# permacam.net
KiCad netlist of a schematic drawn in EAGLE
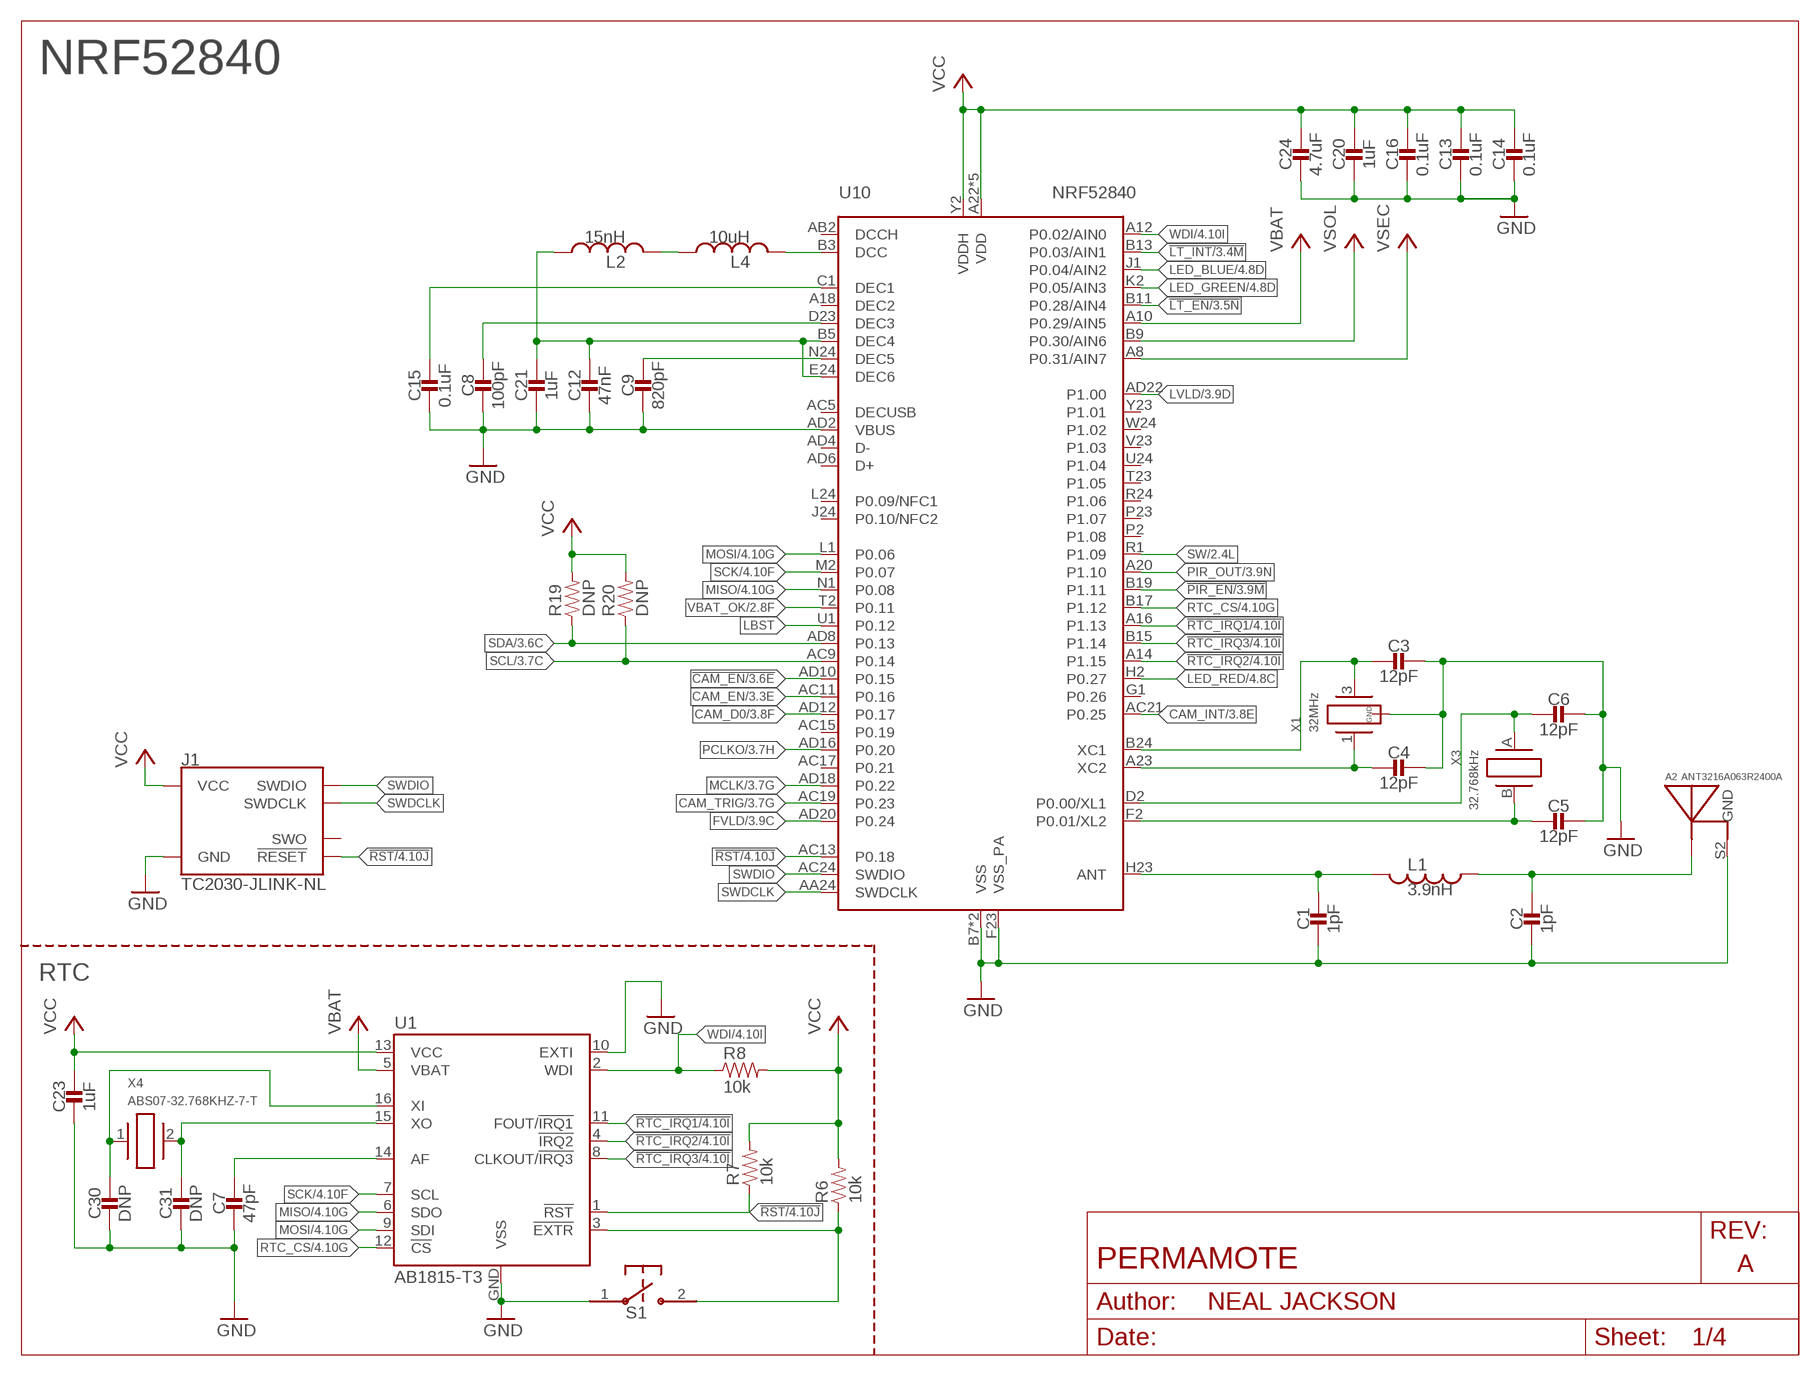
[diagram p0: schematic, sheet 1]
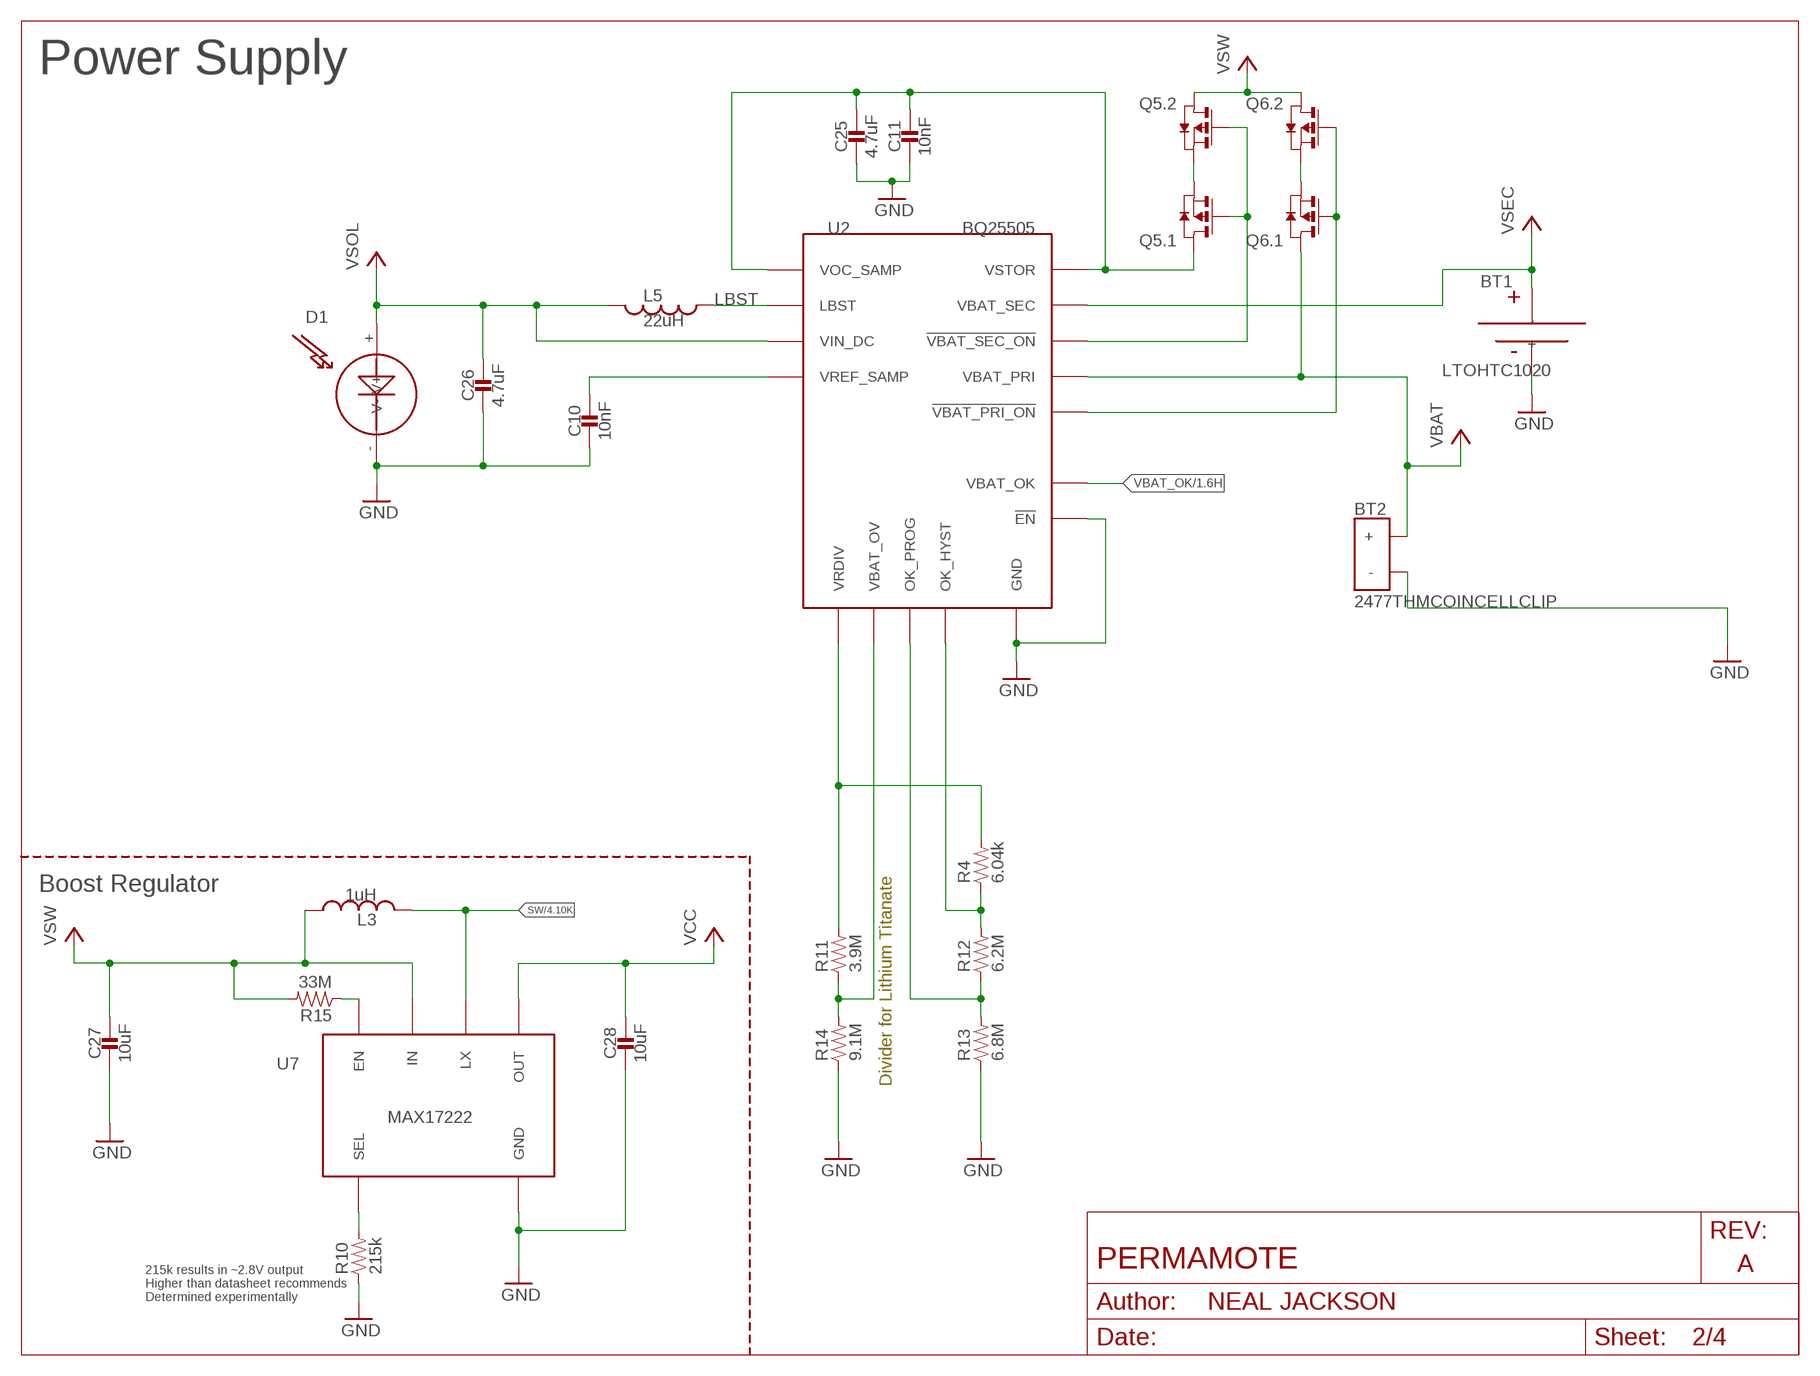
[diagram p1: schematic, sheet 2]
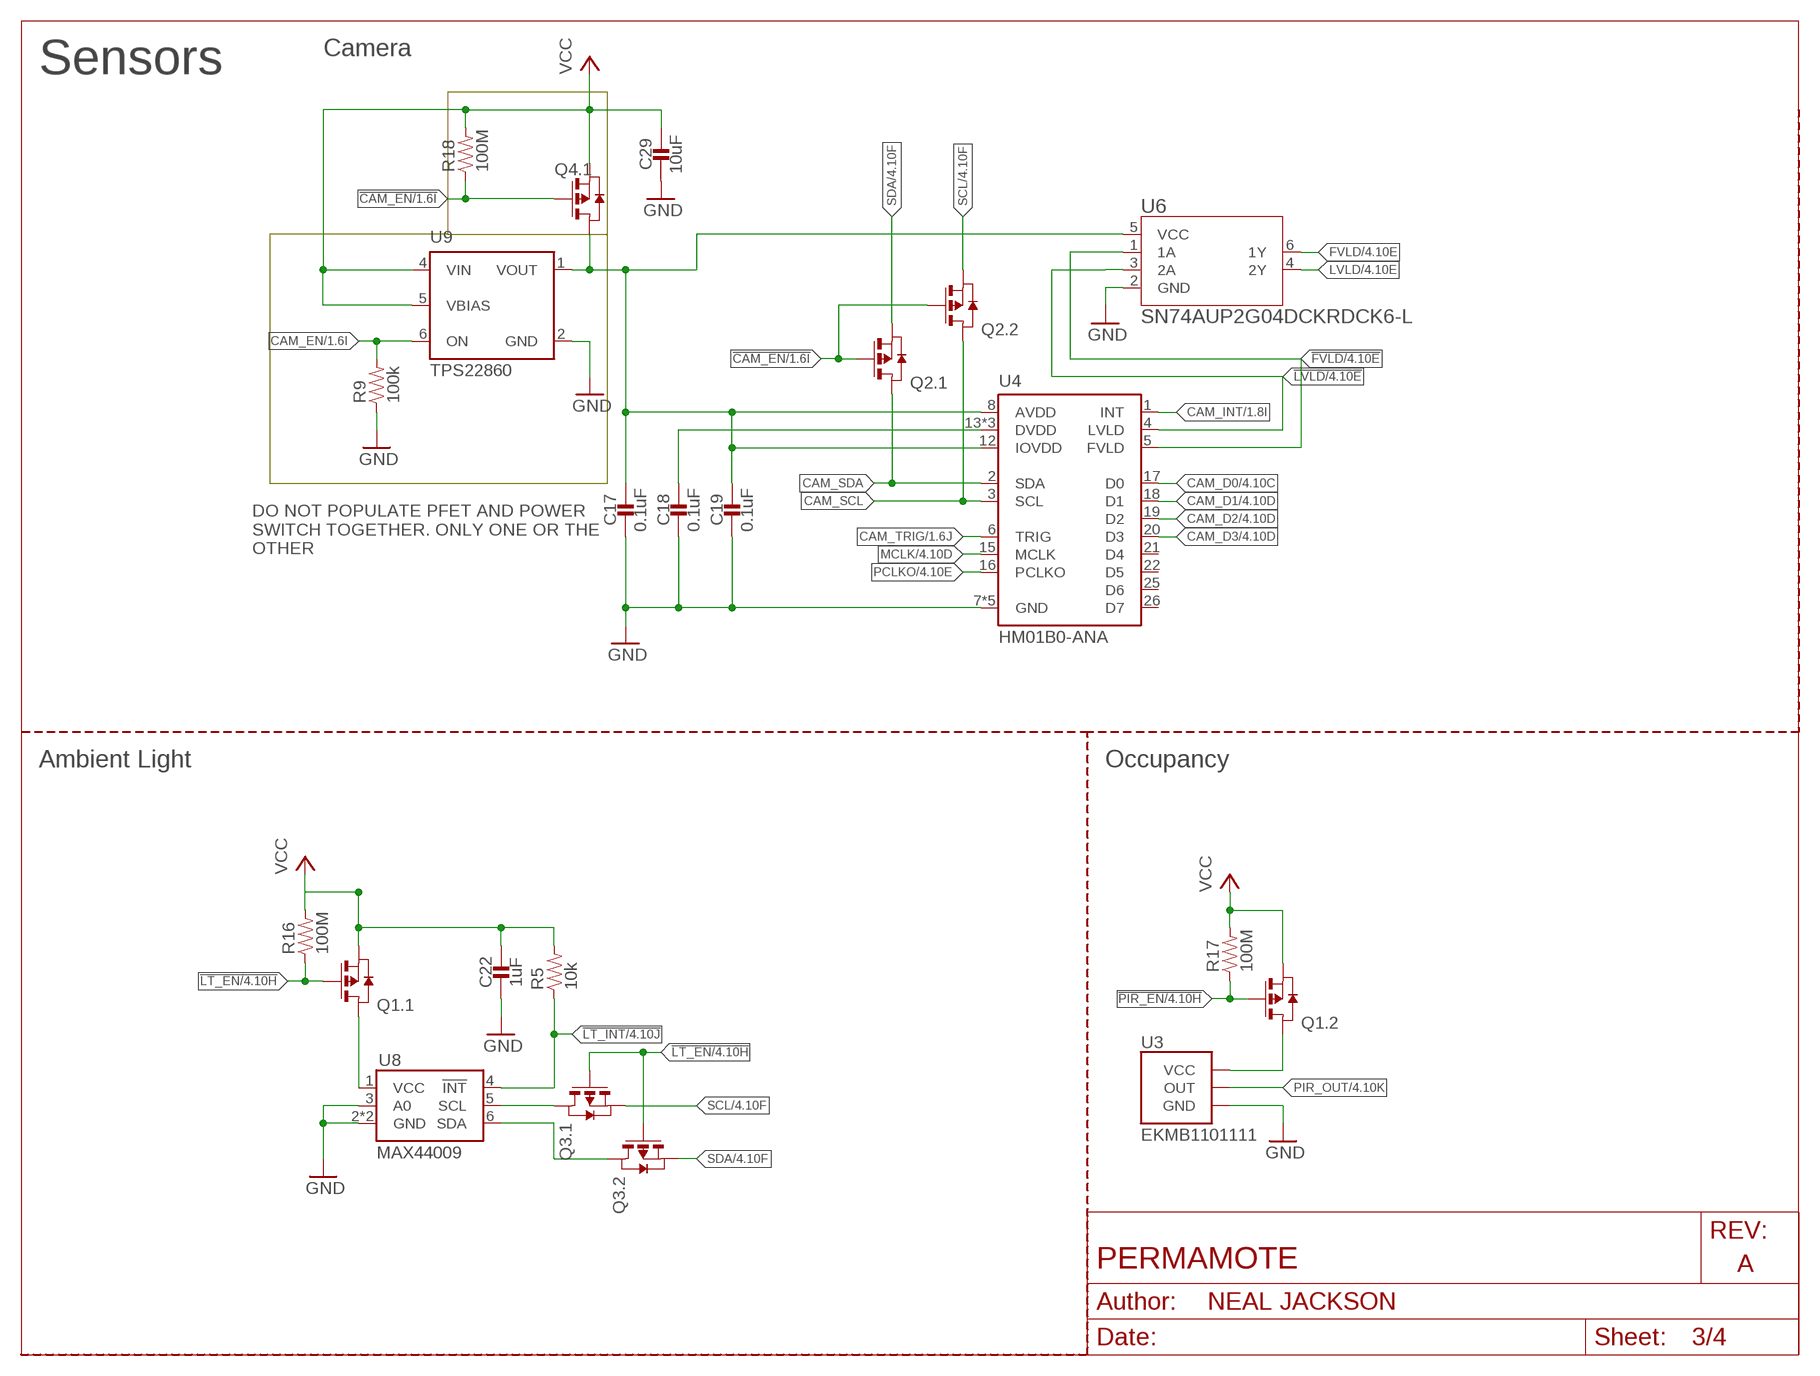
[diagram p2: schematic, sheet 3]
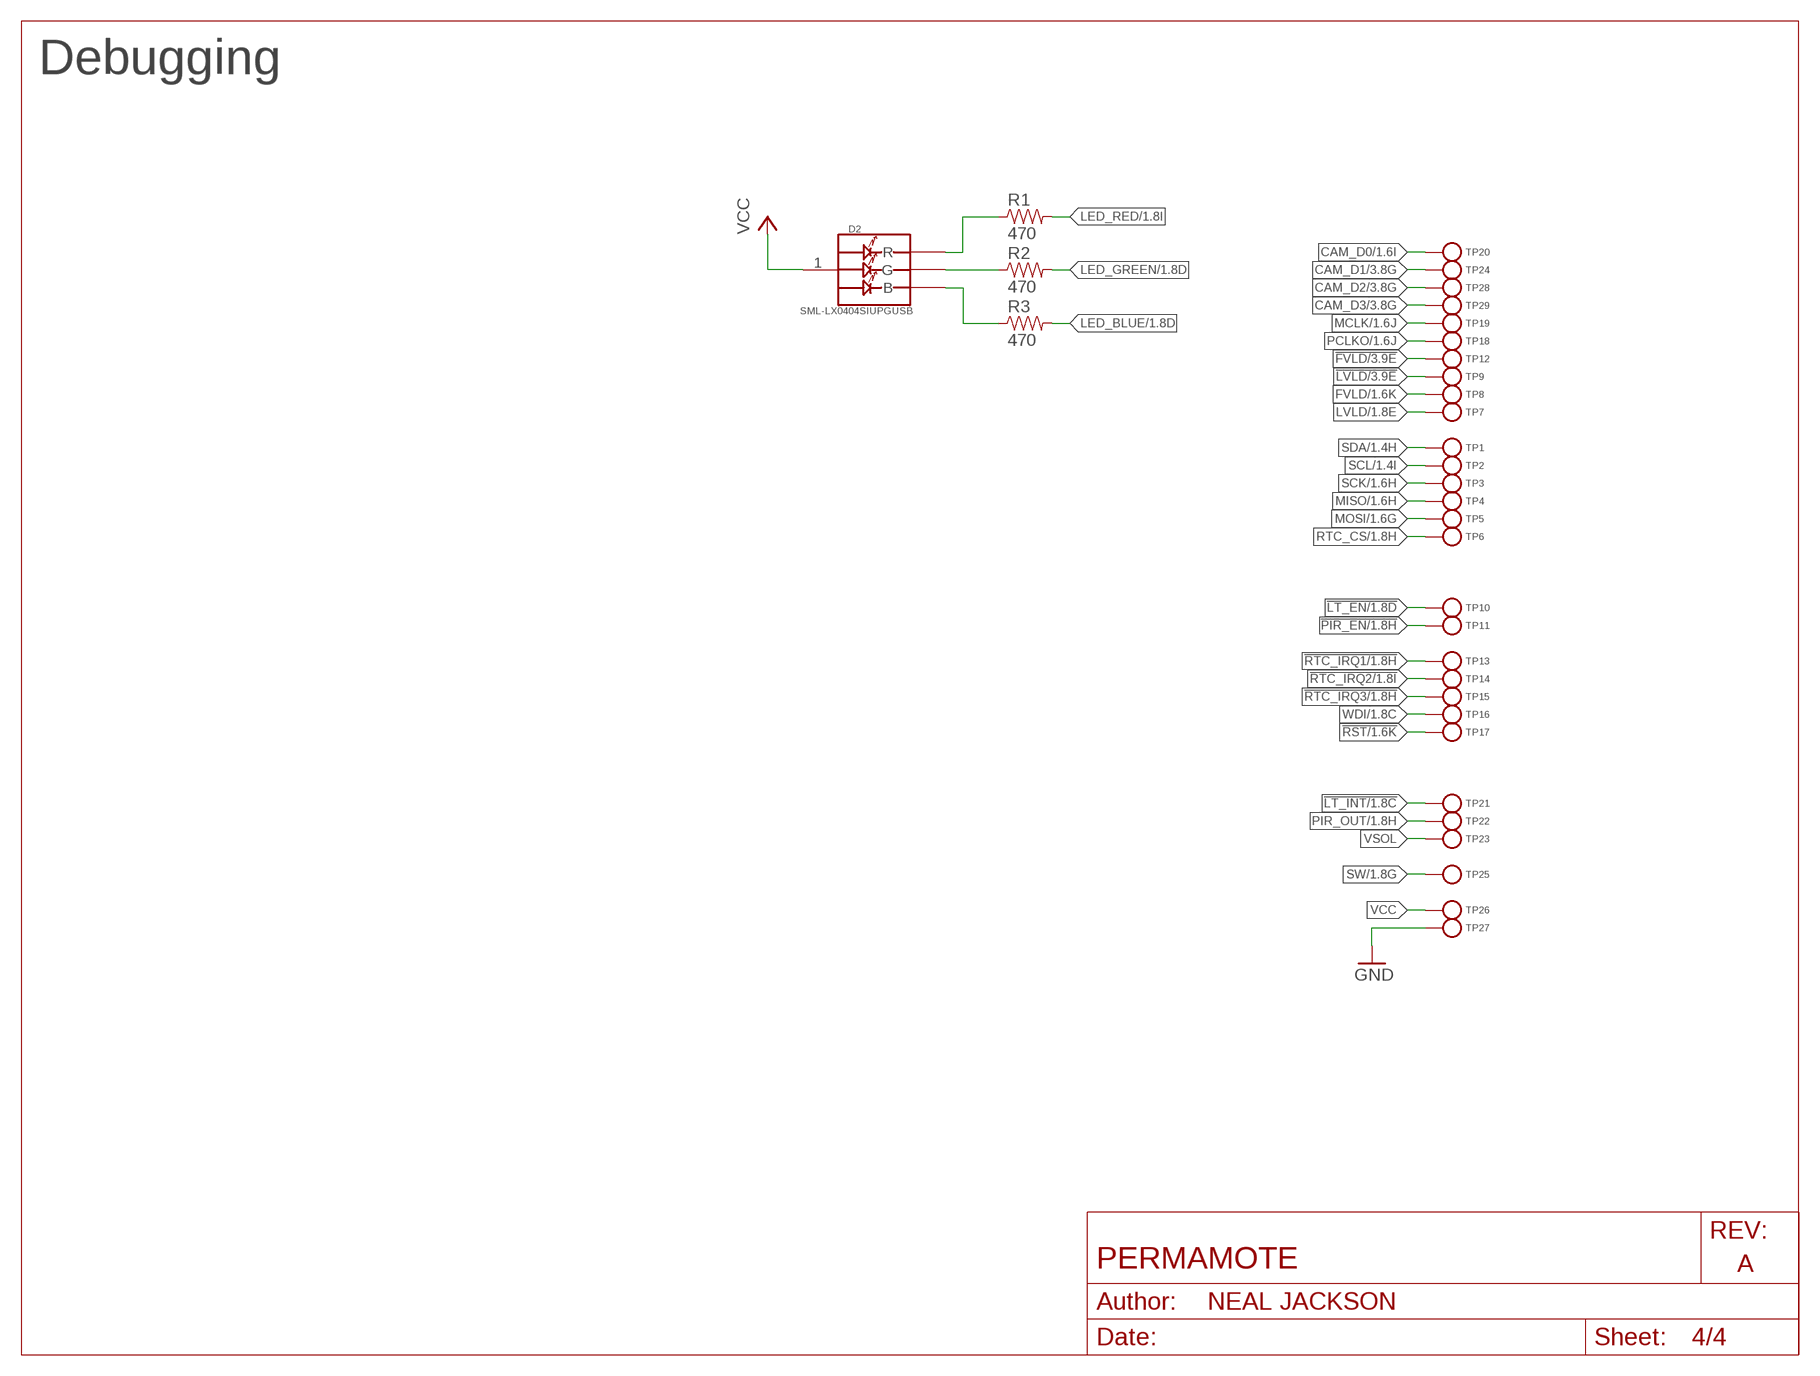
[diagram p3: schematic, sheet 4]

(export (version "E")
  (design (tool "Eeschema 10.0.6"))
  (components
    (comp (ref "C17")
      (value "0.1uF")
      (footprint "eagle-import:0402_CAP")
      (fields (field (name "MPN") "GRM155R71C104KA88J "))
      (libsource (lib "eagle-import") (part "CAPACITOR0402_CAP"))
    )
    (comp (ref "C18")
      (value "0.1uF")
      (footprint "eagle-import:0402_CAP")
      (fields (field (name "MPN") "GRM155R71C104KA88J "))
      (libsource (lib "eagle-import") (part "CAPACITOR0402_CAP"))
    )
    (comp (ref "C19")
      (value "0.1uF")
      (footprint "eagle-import:0402_CAP")
      (fields (field (name "MPN") "GRM155R71C104KA88J "))
      (libsource (lib "eagle-import") (part "CAPACITOR0402_CAP"))
    )
    (comp (ref "C22")
      (value "1uF")
      (footprint "eagle-import:0402_CAP")
      (fields (field (name "MPN") "GRM155R70G105KA12D "))
      (libsource (lib "eagle-import") (part "CAPACITOR0402_CAP"))
    )
    (comp (ref "C29")
      (value "10uF")
      (footprint "eagle-import:0603_CAP")
      (fields (field (name "MPN") "GRM188R60J106ME47D "))
      (libsource (lib "eagle-import") (part "CAPACITOR0603_CAP"))
    )
    (comp (ref "Q1")
      (value "PMDXB950UPEL")
      (footprint "eagle-import:XDFN-6")
      (fields (field (name "MANUFACTURER") "NEXPERIA") (field (name "MPN") "PMDXB950UPELZ"))
      (libsource (lib "eagle-import") (part "PMDXB950UPEL"))
    )
    (comp (ref "Q2")
      (value "PMDXB950UPEL")
      (footprint "eagle-import:XDFN-6")
      (fields (field (name "MANUFACTURER") "NEXPERIA") (field (name "MPN") "PMDXB950UPELZ"))
      (libsource (lib "eagle-import") (part "PMDXB950UPEL"))
    )
    (comp (ref "Q3")
      (value "PMDXB950UPEL")
      (footprint "eagle-import:XDFN-6")
      (fields (field (name "MANUFACTURER") "NEXPERIA") (field (name "MPN") "PMDXB950UPELZ"))
      (libsource (lib "eagle-import") (part "PMDXB950UPEL"))
    )
    (comp (ref "Q4")
      (value "PMDXB950UPEL")
      (footprint "eagle-import:XDFN-6")
      (fields (field (name "MANUFACTURER") "NEXPERIA") (field (name "MPN") "PMDXB950UPELZ"))
      (libsource (lib "eagle-import") (part "PMDXB950UPEL"))
    )
    (comp (ref "R5")
      (value "10k")
      (footprint "eagle-import:0402_RES")
      (fields (field (name "MPN") "RC0402JR-0710KL"))
      (libsource (lib "eagle-import") (part "RESISTOR0402_RES"))
    )
    (comp (ref "R9")
      (value "100k")
      (footprint "eagle-import:0402_RES")
      (fields (field (name "MPN") "RC0402JR-07100KL"))
      (libsource (lib "eagle-import") (part "RESISTOR0402_RES"))
    )
    (comp (ref "R16")
      (value "100M")
      (footprint "eagle-import:0402_RES")
      (fields (field (name "MPN") "HMC0402JT100M "))
      (libsource (lib "eagle-import") (part "RESISTOR0402_RES"))
    )
    (comp (ref "R17")
      (value "100M")
      (footprint "eagle-import:0402_RES")
      (fields (field (name "MPN") "HMC0402JT100M "))
      (libsource (lib "eagle-import") (part "RESISTOR0402_RES"))
    )
    (comp (ref "R18")
      (value "100M")
      (footprint "eagle-import:0402_RES")
      (fields (field (name "MPN") "HMC0402JT100M "))
      (libsource (lib "eagle-import") (part "RESISTOR0402_RES"))
    )
    (comp (ref "U3")
      (value "EKMB1101111")
      (footprint "eagle-import:AMN2")
      (fields (field (name "MANUFACTURER") "PANASONIC"))
      (libsource (lib "eagle-import") (part "EKMB1101111"))
    )
    (comp (ref "U4")
      (value "HM01B0-ANA")
      (footprint "eagle-import:NEOPAC-26")
      (fields (field (name "MPN") "HMB01B0-ANA"))
      (libsource (lib "eagle-import") (part "HM01B0-ANA"))
    )
    (comp (ref "U6")
      (value "SN74AUP2G04DCKRDCK6-L")
      (footprint "eagle-import:DCK6-L")
      (fields (field (name "MANUFACTURER_PART_NUMBER") "SN74AUP2G04DCKR"))
      (libsource (lib "eagle-import") (part "SN74AUP2G04DCKRDCK6-L"))
    )
    (comp (ref "U8")
      (value "MAX44009")
      (footprint "eagle-import:UDFN-6-EXPOSED")
      (fields (field (name "MANUFACTURER") "MAXIM") (field (name "MPN") "MAX44009EDT+T"))
      (libsource (lib "eagle-import") (part "MAX44009"))
    )
    (comp (ref "U9")
      (value "TPS22860")
      (footprint "eagle-import:SOT-23-6")
      (fields (field (name "MPN") "TPS22860DBVR"))
      (libsource (lib "eagle-import") (part "TPS22860"))
    )
    (comp (ref "D2")
      (value "SML-LX0404SIUPGUSB")
      (footprint "eagle-import:1MM_SQ_4PAD")
      (fields (field (name "MANUFACTURER") "Lumex Opto"))
      (libsource (lib "eagle-import") (part "SML-LX0404SIUPGUSB"))
    )
    (comp (ref "R1")
      (value "470")
      (footprint "eagle-import:0402_RES")
      (fields (field (name "MPN") "RC0402JR-07470RL "))
      (libsource (lib "eagle-import") (part "RESISTOR0402_RES"))
    )
    (comp (ref "R2")
      (value "470")
      (footprint "eagle-import:0402_RES")
      (fields (field (name "MPN") "RC0402JR-07470RL "))
      (libsource (lib "eagle-import") (part "RESISTOR0402_RES"))
    )
    (comp (ref "R3")
      (value "470")
      (footprint "eagle-import:0402_RES")
      (fields (field (name "MPN") "RC0402JR-07470RL "))
      (libsource (lib "eagle-import") (part "RESISTOR0402_RES"))
    )
    (comp (ref "TP1")
      (value "TEST-POINT")
      (footprint "eagle-import:PAD.03X.03")
      (libsource (lib "eagle-import") (part "TEST-POINT"))
    )
    (comp (ref "TP2")
      (value "TEST-POINT")
      (footprint "eagle-import:PAD.03X.03")
      (libsource (lib "eagle-import") (part "TEST-POINT"))
    )
    (comp (ref "TP3")
      (value "TEST-POINT")
      (footprint "eagle-import:PAD.03X.03")
      (libsource (lib "eagle-import") (part "TEST-POINT"))
    )
    (comp (ref "TP4")
      (value "TEST-POINT")
      (footprint "eagle-import:PAD.03X.03")
      (libsource (lib "eagle-import") (part "TEST-POINT"))
    )
    (comp (ref "TP5")
      (value "TEST-POINT")
      (footprint "eagle-import:PAD.03X.03")
      (libsource (lib "eagle-import") (part "TEST-POINT"))
    )
    (comp (ref "TP6")
      (value "TEST-POINT")
      (footprint "eagle-import:PAD.03X.03")
      (libsource (lib "eagle-import") (part "TEST-POINT"))
    )
    (comp (ref "TP7")
      (value "TEST-POINT")
      (footprint "eagle-import:PAD.03X.03")
      (libsource (lib "eagle-import") (part "TEST-POINT"))
    )
    (comp (ref "TP8")
      (value "TEST-POINT")
      (footprint "eagle-import:PAD.03X.03")
      (libsource (lib "eagle-import") (part "TEST-POINT"))
    )
    (comp (ref "TP9")
      (value "TEST-POINT")
      (footprint "eagle-import:PAD.03X.03")
      (libsource (lib "eagle-import") (part "TEST-POINT"))
    )
    (comp (ref "TP10")
      (value "TEST-POINT")
      (footprint "eagle-import:PAD.03X.03")
      (libsource (lib "eagle-import") (part "TEST-POINT"))
    )
    (comp (ref "TP11")
      (value "TEST-POINT")
      (footprint "eagle-import:PAD.03X.03")
      (libsource (lib "eagle-import") (part "TEST-POINT"))
    )
    (comp (ref "TP12")
      (value "TEST-POINT")
      (footprint "eagle-import:PAD.03X.03")
      (libsource (lib "eagle-import") (part "TEST-POINT"))
    )
    (comp (ref "TP13")
      (value "TEST-POINT")
      (footprint "eagle-import:PAD.03X.03")
      (libsource (lib "eagle-import") (part "TEST-POINT"))
    )
    (comp (ref "TP14")
      (value "TEST-POINT")
      (footprint "eagle-import:PAD.03X.03")
      (libsource (lib "eagle-import") (part "TEST-POINT"))
    )
    (comp (ref "TP15")
      (value "TEST-POINT")
      (footprint "eagle-import:PAD.03X.03")
      (libsource (lib "eagle-import") (part "TEST-POINT"))
    )
    (comp (ref "TP16")
      (value "TEST-POINT")
      (footprint "eagle-import:PAD.03X.03")
      (libsource (lib "eagle-import") (part "TEST-POINT"))
    )
    (comp (ref "TP17")
      (value "TEST-POINT")
      (footprint "eagle-import:PAD.03X.03")
      (libsource (lib "eagle-import") (part "TEST-POINT"))
    )
    (comp (ref "TP18")
      (value "TEST-POINT")
      (footprint "eagle-import:PAD.03X.03")
      (libsource (lib "eagle-import") (part "TEST-POINT"))
    )
    (comp (ref "TP19")
      (value "TEST-POINT")
      (footprint "eagle-import:PAD.03X.03")
      (libsource (lib "eagle-import") (part "TEST-POINT"))
    )
    (comp (ref "TP20")
      (value "TEST-POINT")
      (footprint "eagle-import:PAD.03X.03")
      (libsource (lib "eagle-import") (part "TEST-POINT"))
    )
    (comp (ref "TP21")
      (value "TEST-POINT")
      (footprint "eagle-import:PAD.03X.03")
      (libsource (lib "eagle-import") (part "TEST-POINT"))
    )
    (comp (ref "TP22")
      (value "TEST-POINT")
      (footprint "eagle-import:PAD.03X.03")
      (libsource (lib "eagle-import") (part "TEST-POINT"))
    )
    (comp (ref "TP23")
      (value "TEST-POINT")
      (footprint "eagle-import:PAD.03X.03")
      (libsource (lib "eagle-import") (part "TEST-POINT"))
    )
    (comp (ref "TP24")
      (value "TEST-POINT")
      (footprint "eagle-import:PAD.03X.03")
      (libsource (lib "eagle-import") (part "TEST-POINT"))
    )
    (comp (ref "TP25")
      (value "TEST-POINT")
      (footprint "eagle-import:PAD.03X.03")
      (libsource (lib "eagle-import") (part "TEST-POINT"))
    )
    (comp (ref "TP26")
      (value "TEST-POINT")
      (footprint "eagle-import:PAD.03X.03")
      (libsource (lib "eagle-import") (part "TEST-POINT"))
    )
    (comp (ref "TP27")
      (value "TEST-POINT")
      (footprint "eagle-import:PAD.03X.03")
      (libsource (lib "eagle-import") (part "TEST-POINT"))
    )
    (comp (ref "TP28")
      (value "TEST-POINT")
      (footprint "eagle-import:PAD.03X.03")
      (libsource (lib "eagle-import") (part "TEST-POINT"))
    )
    (comp (ref "TP29")
      (value "TEST-POINT")
      (footprint "eagle-import:PAD.03X.03")
      (libsource (lib "eagle-import") (part "TEST-POINT"))
    )
    (comp (ref "A2")
      (value "ANT3216A063R2400A")
      (footprint "eagle-import:ANT3216A063R2400A")
      (fields (field (name "MANUFACTURER") "YAGEO"))
      (libsource (lib "eagle-import") (part "ANT3216A063R2400A"))
    )
    (comp (ref "C1")
      (value "1pF")
      (footprint "eagle-import:0402_CAP")
      (fields (field (name "MPN") "CL05C010CB5NNNC"))
      (libsource (lib "eagle-import") (part "CAPACITOR0402_CAP"))
    )
    (comp (ref "C2")
      (value "1pF")
      (footprint "eagle-import:0402_CAP")
      (fields (field (name "MPN") "CL05C010CB5NNNC"))
      (libsource (lib "eagle-import") (part "CAPACITOR0402_CAP"))
    )
    (comp (ref "C3")
      (value "12pF")
      (footprint "eagle-import:0402_CAP")
      (fields (field (name "MPN") "GRM1555C1H120GA01D "))
      (libsource (lib "eagle-import") (part "CAPACITOR0402_CAP"))
    )
    (comp (ref "C4")
      (value "12pF")
      (footprint "eagle-import:0402_CAP")
      (fields (field (name "MPN") "GRM1555C1H120GA01D "))
      (libsource (lib "eagle-import") (part "CAPACITOR0402_CAP"))
    )
    (comp (ref "C5")
      (value "12pF")
      (footprint "eagle-import:0402_CAP")
      (fields (field (name "MPN") "GRM1555C1H120GA01D "))
      (libsource (lib "eagle-import") (part "CAPACITOR0402_CAP"))
    )
    (comp (ref "C6")
      (value "12pF")
      (footprint "eagle-import:0402_CAP")
      (fields (field (name "MPN") "GRM1555C1H120GA01D "))
      (libsource (lib "eagle-import") (part "CAPACITOR0402_CAP"))
    )
    (comp (ref "C7")
      (value "47pF")
      (footprint "eagle-import:0402_CAP")
      (fields (field (name "MPN") "GRM1555C1H470JA01D "))
      (libsource (lib "eagle-import") (part "CAPACITOR0402_CAP"))
    )
    (comp (ref "C8")
      (value "100pF")
      (footprint "eagle-import:0402_CAP")
      (fields (field (name "MPN") "GRM1555C1H101JA01D "))
      (libsource (lib "eagle-import") (part "CAPACITOR0402_CAP"))
    )
    (comp (ref "C9")
      (value "820pF")
      (footprint "eagle-import:0402_CAP")
      (fields (field (name "MPN") "CL05B821KO5NNNC"))
      (libsource (lib "eagle-import") (part "CAPACITOR0402_CAP"))
    )
    (comp (ref "C12")
      (value "47nF")
      (footprint "eagle-import:0402_CAP")
      (fields (field (name "MPN") "C1005X7R1C473K050BC "))
      (libsource (lib "eagle-import") (part "CAPACITOR0402_CAP"))
    )
    (comp (ref "C13")
      (value "0.1uF")
      (footprint "eagle-import:0402_CAP")
      (fields (field (name "MPN") "GRM155R71C104KA88J "))
      (libsource (lib "eagle-import") (part "CAPACITOR0402_CAP"))
    )
    (comp (ref "C14")
      (value "0.1uF")
      (footprint "eagle-import:0402_CAP")
      (fields (field (name "MPN") "GRM155R71C104KA88J "))
      (libsource (lib "eagle-import") (part "CAPACITOR0402_CAP"))
    )
    (comp (ref "C15")
      (value "0.1uF")
      (footprint "eagle-import:0402_CAP")
      (fields (field (name "MPN") "GRM155R71C104KA88J "))
      (libsource (lib "eagle-import") (part "CAPACITOR0402_CAP"))
    )
    (comp (ref "C16")
      (value "0.1uF")
      (footprint "eagle-import:0402_CAP")
      (fields (field (name "MPN") "GRM155R71C104KA88J "))
      (libsource (lib "eagle-import") (part "CAPACITOR0402_CAP"))
    )
    (comp (ref "C20")
      (value "1uF")
      (footprint "eagle-import:0402_CAP")
      (fields (field (name "MPN") "GRM155R70G105KA12D "))
      (libsource (lib "eagle-import") (part "CAPACITOR0402_CAP"))
    )
    (comp (ref "C21")
      (value "1uF")
      (footprint "eagle-import:0402_CAP")
      (fields (field (name "MPN") "GRM155R70G105KA12D "))
      (libsource (lib "eagle-import") (part "CAPACITOR0402_CAP"))
    )
    (comp (ref "C23")
      (value "1uF")
      (footprint "eagle-import:0402_CAP")
      (fields (field (name "MPN") "GRM155R70G105KA12D "))
      (libsource (lib "eagle-import") (part "CAPACITOR0402_CAP"))
    )
    (comp (ref "C24")
      (value "4.7uF")
      (footprint "eagle-import:0402_CAP")
      (fields (field (name "MPN") "C1005X5R0J475K050BC "))
      (libsource (lib "eagle-import") (part "CAPACITOR0402_CAP"))
    )
    (comp (ref "C30")
      (value "DNP")
      (footprint "eagle-import:0402_CAP")
      (libsource (lib "eagle-import") (part "CAPACITOR0402_CAP"))
    )
    (comp (ref "C31")
      (value "DNP")
      (footprint "eagle-import:0402_CAP")
      (libsource (lib "eagle-import") (part "CAPACITOR0402_CAP"))
    )
    (comp (ref "J1")
      (value "TC2030-JLINK-NL")
      (footprint "eagle-import:TC2030-IDC-NL")
      (libsource (lib "eagle-import") (part "TC2030-JLINK-NL"))
    )
    (comp (ref "L1")
      (value "3.9nH")
      (footprint "eagle-import:0402_CAP")
      (fields (field (name "MPN") "LQP15MN3N9B02D"))
      (libsource (lib "eagle-import") (part "INDUCTOR0402"))
    )
    (comp (ref "L2")
      (value "15nH")
      (footprint "eagle-import:0402_CAP")
      (fields (field (name "MPN") "HK100515NJ-T "))
      (libsource (lib "eagle-import") (part "INDUCTOR0402"))
    )
    (comp (ref "L4")
      (value "10uH")
      (footprint "eagle-import:0603_CAP")
      (fields (field (name "MPN") "LQM18FN100M00D "))
      (libsource (lib "eagle-import") (part "INDUCTOR0603"))
    )
    (comp (ref "R6")
      (value "10k")
      (footprint "eagle-import:0402_RES")
      (fields (field (name "MPN") "RC0402JR-0710KL"))
      (libsource (lib "eagle-import") (part "RESISTOR0402_RES"))
    )
    (comp (ref "R7")
      (value "10k")
      (footprint "eagle-import:0402_RES")
      (fields (field (name "MPN") "RC0402JR-0710KL"))
      (libsource (lib "eagle-import") (part "RESISTOR0402_RES"))
    )
    (comp (ref "R8")
      (value "10k")
      (footprint "eagle-import:0402_RES")
      (fields (field (name "MPN") "RC0402JR-0710KL"))
      (libsource (lib "eagle-import") (part "RESISTOR0402_RES"))
    )
    (comp (ref "R19")
      (value "DNP")
      (footprint "eagle-import:0402_RES")
      (libsource (lib "eagle-import") (part "RESISTOR0402_RES"))
    )
    (comp (ref "R20")
      (value "DNP")
      (footprint "eagle-import:0402_RES")
      (libsource (lib "eagle-import") (part "RESISTOR0402_RES"))
    )
    (comp (ref "S1")
      (value "B3U-1000P")
      (footprint "eagle-import:B3U-1000P")
      (fields (field (name "MANUFACTURER") "Omron"))
      (libsource (lib "eagle-import") (part "B3U-1000P"))
    )
    (comp (ref "U1")
      (value "AB1815-T3")
      (footprint "eagle-import:QFN-16-3MM")
      (fields (field (name "MANUFACTURER") "Abracon"))
      (libsource (lib "eagle-import") (part "AB1815-T3"))
    )
    (comp (ref "U10")
      (value "NRF52840")
      (footprint "eagle-import:AQFN73")
      (fields (field (name "MANUFACTURER") "NORIDIC SEMICONDUCTOR"))
      (libsource (lib "eagle-import") (part "NRF52840"))
    )
    (comp (ref "X1")
      (value "32MHz")
      (footprint "eagle-import:TXC-7V")
      (fields (field (name "MANUFACTURER") "TXC CORPORATION") (field (name "MPN") "7M-32.000MAHV-T"))
      (libsource (lib "eagle-import") (part "7V-32.000MAHV-T"))
    )
    (comp (ref "X3")
      (value "32.768kHz")
      (footprint "eagle-import:ABS05")
      (fields (field (name "MANUFACTURER") "Abracon") (field (name "MPN") "ABS05-32.768KHZ-9-T"))
      (libsource (lib "eagle-import") (part "ABS05-32.768KHZ-9-T"))
    )
    (comp (ref "X4")
      (value "ABS07-32.768KHZ-7-T")
      (footprint "eagle-import:2-SMD")
      (fields (field (name "MANUFACTURER") "ABRACON") (field (name "MPN") "ABS07-32.768KHZ-7-T "))
      (libsource (lib "eagle-import") (part "ABS07-32.768KHZ-7-T"))
    )
    (comp (ref "BT1")
      (value "LTOHTC1020")
      (footprint "eagle-import:1020")
      (libsource (lib "eagle-import") (part "LTOHTC1020"))
    )
    (comp (ref "BT2")
      (value "2477THMCOINCELLCLIP")
      (footprint "eagle-import:2477THMCOINCLIP")
      (fields (field (name "MANUFACTURER") "Keystone") (field (name "MPN") "3039"))
      (libsource (lib "eagle-import") (part "2477THMCOINCELLCLIP"))
    )
    (comp (ref "C10")
      (value "10nF")
      (footprint "eagle-import:0402_CAP")
      (fields (field (name "MPN") "GRM155R71H103KA88D "))
      (libsource (lib "eagle-import") (part "CAPACITOR0402_CAP"))
    )
    (comp (ref "C11")
      (value "10nF")
      (footprint "eagle-import:0402_CAP")
      (fields (field (name "MPN") "GRM155R71H103KA88D "))
      (libsource (lib "eagle-import") (part "CAPACITOR0402_CAP"))
    )
    (comp (ref "C25")
      (value "4.7uF")
      (footprint "eagle-import:0402_CAP")
      (fields (field (name "MPN") "C1005X5R0J475K050BC "))
      (libsource (lib "eagle-import") (part "CAPACITOR0402_CAP"))
    )
    (comp (ref "C26")
      (value "4.7uF")
      (footprint "eagle-import:0402_CAP")
      (fields (field (name "MPN") "C1005X5R0J475K050BC "))
      (libsource (lib "eagle-import") (part "CAPACITOR0402_CAP"))
    )
    (comp (ref "C27")
      (value "10uF")
      (footprint "eagle-import:0603_CAP")
      (fields (field (name "MPN") "GRM188R60J106ME47D "))
      (libsource (lib "eagle-import") (part "CAPACITOR0603_CAP"))
    )
    (comp (ref "C28")
      (value "10uF")
      (footprint "eagle-import:0603_CAP")
      (fields (field (name "MPN") "GRM188R60J106ME47D "))
      (libsource (lib "eagle-import") (part "CAPACITOR0603_CAP"))
    )
    (comp (ref "D1")
      (value "SOLARCELLHOLES")
      (footprint "eagle-import:SOLAR_HOLES")
      (fields (field (name "MPN") "AM-1454CA"))
      (libsource (lib "eagle-import") (part "SOLARCELLHOLES"))
    )
    (comp (ref "L3")
      (value "1uH")
      (footprint "eagle-import:IHL-1212BZ-11")
      (fields
        (field (name "MANUFACTURER") "Vishay Dale")
        (field (name "MPN") "IHLP1212BZER2R2M11")
        (field (name "DIGIKEY") "541-1319-1-ND")
        (field (name "MPN_1") "IHLP1212BZER1R0M11")
      )
      (libsource (lib "eagle-import") (part "INDUCTORIHL"))
    )
    (comp (ref "L5")
      (value "22uH")
      (footprint "eagle-import:74437324220")
      (fields (field (name "DIGIKEY") "732-3340-1-ND") (field (name "MPN") "74437324220 "))
      (libsource (lib "eagle-import") (part "INDUCTOR74437324220"))
    )
    (comp (ref "Q5")
      (value "PMDXB950UPEL")
      (footprint "eagle-import:XDFN-6")
      (fields (field (name "MANUFACTURER") "NEXPERIA") (field (name "MPN") "PMDXB950UPELZ"))
      (libsource (lib "eagle-import") (part "PMDXB950UPEL"))
    )
    (comp (ref "Q6")
      (value "PMDXB950UPEL")
      (footprint "eagle-import:XDFN-6")
      (fields (field (name "MANUFACTURER") "NEXPERIA") (field (name "MPN") "PMDXB950UPELZ"))
      (libsource (lib "eagle-import") (part "PMDXB950UPEL"))
    )
    (comp (ref "R4")
      (value "6.04k")
      (footprint "eagle-import:0402_RES")
      (fields (field (name "MPN") "RC0402FR-076K04L"))
      (libsource (lib "eagle-import") (part "RESISTOR0402_RES"))
    )
    (comp (ref "R10")
      (value "215k")
      (footprint "eagle-import:0603-RES")
      (fields (field (name "MPN") "RC0603FR-07215KL"))
      (libsource (lib "eagle-import") (part "RESISTOR0603_RES"))
    )
    (comp (ref "R11")
      (value "3.9M")
      (footprint "eagle-import:0402_RES")
      (fields (field (name "MPN") "RC0402JR-073M9L"))
      (libsource (lib "eagle-import") (part "RESISTOR0402_RES"))
    )
    (comp (ref "R12")
      (value "6.2M")
      (footprint "eagle-import:0402_RES")
      (fields (field (name "MPN") "RC0402JR-076M2L"))
      (libsource (lib "eagle-import") (part "RESISTOR0402_RES"))
    )
    (comp (ref "R13")
      (value "6.8M")
      (footprint "eagle-import:0402_RES")
      (fields (field (name "MPN") "RC0402JR-076M8L"))
      (libsource (lib "eagle-import") (part "RESISTOR0402_RES"))
    )
    (comp (ref "R14")
      (value "9.1M")
      (footprint "eagle-import:0402_RES")
      (fields (field (name "MPN") "RC0402JR-079M1L"))
      (libsource (lib "eagle-import") (part "RESISTOR0402_RES"))
    )
    (comp (ref "R15")
      (value "33M")
      (footprint "eagle-import:0603-RES")
      (fields (field (name "MPN") "HMC0603JT33M0 "))
      (libsource (lib "eagle-import") (part "RESISTOR0603_RES"))
    )
    (comp (ref "U2")
      (value "BQ25505")
      (footprint "eagle-import:S-PVQFN-N20-RGR")
      (fields (field (name "MANUFACTURER") "TI") (field (name "MPN") "BQ25505RGRR"))
      (libsource (lib "eagle-import") (part "BQ25505"))
    )
    (comp (ref "U7")
      (value "MAX17222")
      (footprint "eagle-import:UDFN-6-MAXIM")
      (fields (field (name "MANUFACTURER") "MAXIM INTEGRATED") (field (name "MPN") "MAX17222ELT+T"))
      (libsource (lib "eagle-import") (part "MAX17222"))
    )
  )
  (nets
    (net (code "1") (name "CAM_D0") (class "Default")
      (node (ref "TP20") (pin "P$1") (pinfunction "TESTPOINT_P$1") (pintype "bidirectional"))
      (node (ref "U10") (pin "AD12") (pinfunction "P0.17_AD12") (pintype "bidirectional"))
      (node (ref "U4") (pin "17") (pinfunction "D0_17") (pintype "bidirectional"))
    )
    (net (code "2") (name "CAM_D1") (class "Default")
      (node (ref "TP24") (pin "P$1") (pinfunction "TESTPOINT_P$1") (pintype "bidirectional"))
      (node (ref "U4") (pin "18") (pinfunction "D1_18") (pintype "bidirectional"))
    )
    (net (code "3") (name "CAM_D2") (class "Default")
      (node (ref "TP28") (pin "P$1") (pinfunction "TESTPOINT_P$1") (pintype "bidirectional"))
      (node (ref "U4") (pin "19") (pinfunction "D2_19") (pintype "bidirectional"))
    )
    (net (code "4") (name "CAM_D3") (class "Default")
      (node (ref "TP29") (pin "P$1") (pinfunction "TESTPOINT_P$1") (pintype "bidirectional"))
      (node (ref "U4") (pin "20") (pinfunction "D3_20") (pintype "bidirectional"))
    )
    (net (code "5") (name "CAM_EN") (class "Default")
      (node (ref "R9") (pin "2") (pinfunction "2_2") (pintype "passive"))
      (node (ref "U10") (pin "AC11") (pinfunction "P0.16_AC11") (pintype "bidirectional"))
      (node (ref "U9") (pin "6") (pinfunction "ON_6") (pintype "bidirectional"))
    )
    (net (code "6") (name "CAM_INT") (class "Default")
      (node (ref "U10") (pin "AC21") (pinfunction "P0.25_AC21") (pintype "bidirectional"))
      (node (ref "U4") (pin "1") (pinfunction "INT_1") (pintype "bidirectional"))
    )
    (net (code "7") (name "CAM_SCL") (class "Default")
      (node (ref "Q2") (pin "3") (pinfunction "D_3") (pintype "passive"))
      (node (ref "U4") (pin "3") (pinfunction "SCL_3") (pintype "bidirectional"))
    )
    (net (code "8") (name "CAM_SDA") (class "Default")
      (node (ref "Q2") (pin "6") (pinfunction "D_6") (pintype "passive"))
      (node (ref "U4") (pin "2") (pinfunction "SDA_2") (pintype "bidirectional"))
    )
    (net (code "9") (name "CAM_TRIG") (class "Default")
      (node (ref "U10") (pin "AC19") (pinfunction "P0.23_AC19") (pintype "bidirectional"))
      (node (ref "U4") (pin "6") (pinfunction "TRIG_6") (pintype "bidirectional"))
    )
    (net (code "10") (name "FVLD") (class "Default")
      (node (ref "TP8") (pin "P$1") (pinfunction "TESTPOINT_P$1") (pintype "bidirectional"))
      (node (ref "U10") (pin "AD20") (pinfunction "P0.24_AD20") (pintype "bidirectional"))
      (node (ref "U6") (pin "6") (pinfunction "1Y_6") (pintype "output"))
    )
    (net (code "11") (name "GND") (class "Default")
      (node (ref "A2") (pin "S2") (pinfunction "GND_S2") (pintype "bidirectional"))
      (node (ref "BT1") (pin "-") (pinfunction "-_-") (pintype "bidirectional"))
      (node (ref "BT2") (pin "GND") (pinfunction "-_GND") (pintype "bidirectional"))
      (node (ref "C1") (pin "2") (pinfunction "2_2") (pintype "bidirectional"))
      (node (ref "C10") (pin "2") (pinfunction "2_2") (pintype "bidirectional"))
      (node (ref "C11") (pin "2") (pinfunction "2_2") (pintype "bidirectional"))
      (node (ref "C12") (pin "2") (pinfunction "2_2") (pintype "bidirectional"))
      (node (ref "C13") (pin "2") (pinfunction "2_2") (pintype "bidirectional"))
      (node (ref "C14") (pin "2") (pinfunction "2_2") (pintype "bidirectional"))
      (node (ref "C15") (pin "2") (pinfunction "2_2") (pintype "bidirectional"))
      (node (ref "C16") (pin "2") (pinfunction "2_2") (pintype "bidirectional"))
      (node (ref "C17") (pin "2") (pinfunction "2_2") (pintype "bidirectional"))
      (node (ref "C18") (pin "2") (pinfunction "2_2") (pintype "bidirectional"))
      (node (ref "C19") (pin "2") (pinfunction "2_2") (pintype "bidirectional"))
      (node (ref "C2") (pin "2") (pinfunction "2_2") (pintype "bidirectional"))
      (node (ref "C20") (pin "2") (pinfunction "2_2") (pintype "bidirectional"))
      (node (ref "C21") (pin "2") (pinfunction "2_2") (pintype "bidirectional"))
      (node (ref "C22") (pin "2") (pinfunction "2_2") (pintype "bidirectional"))
      (node (ref "C23") (pin "2") (pinfunction "2_2") (pintype "bidirectional"))
      (node (ref "C24") (pin "2") (pinfunction "2_2") (pintype "bidirectional"))
      (node (ref "C25") (pin "2") (pinfunction "2_2") (pintype "bidirectional"))
      (node (ref "C26") (pin "2") (pinfunction "2_2") (pintype "bidirectional"))
      (node (ref "C27") (pin "2") (pinfunction "2_2") (pintype "bidirectional"))
      (node (ref "C28") (pin "2") (pinfunction "2_2") (pintype "bidirectional"))
      (node (ref "C29") (pin "2") (pinfunction "2_2") (pintype "bidirectional"))
      (node (ref "C3") (pin "1") (pinfunction "1_1") (pintype "bidirectional"))
      (node (ref "C30") (pin "2") (pinfunction "2_2") (pintype "bidirectional"))
      (node (ref "C31") (pin "2") (pinfunction "2_2") (pintype "bidirectional"))
      (node (ref "C4") (pin "1") (pinfunction "1_1") (pintype "bidirectional"))
      (node (ref "C5") (pin "1") (pinfunction "1_1") (pintype "bidirectional"))
      (node (ref "C6") (pin "1") (pinfunction "1_1") (pintype "bidirectional"))
      (node (ref "C7") (pin "2") (pinfunction "2_2") (pintype "bidirectional"))
      (node (ref "C8") (pin "2") (pinfunction "2_2") (pintype "bidirectional"))
      (node (ref "C9") (pin "2") (pinfunction "2_2") (pintype "bidirectional"))
      (node (ref "D1") (pin "-") (pinfunction "V-_-") (pintype "bidirectional"))
      (node (ref "J1") (pin "5") (pinfunction "GND_5") (pintype "bidirectional"))
      (node (ref "R10") (pin "1") (pinfunction "1_1") (pintype "passive"))
      (node (ref "R13") (pin "1") (pinfunction "1_1") (pintype "passive"))
      (node (ref "R14") (pin "1") (pinfunction "1_1") (pintype "passive"))
      (node (ref "R9") (pin "1") (pinfunction "1_1") (pintype "passive"))
      (node (ref "S1") (pin "1") (pinfunction "P$1_1") (pintype "passive"))
      (node (ref "TP27") (pin "P$1") (pinfunction "TESTPOINT_P$1") (pintype "bidirectional"))
      (node (ref "U1") (pin "10") (pinfunction "EXTI_10") (pintype "bidirectional"))
      (node (ref "U1") (pin "GND") (pinfunction "VSS_GND") (pintype "bidirectional"))
      (node (ref "U10") (pin "AD2") (pinfunction "VBUS_AD2") (pintype "bidirectional"))
      (node (ref "U10") (pin "B7") (pinfunction "VSS_B7") (pintype "bidirectional"))
      (node (ref "U10") (pin "F23") (pinfunction "VSS_PA_F23") (pintype "bidirectional"))
      (node (ref "U10") (pin "GND") (pinfunction "VSS_GND") (pintype "bidirectional"))
      (node (ref "U2") (pin "1") (pinfunction "GND_1") (pintype "bidirectional"))
      (node (ref "U2") (pin "15") (pinfunction "GND_15") (pintype "bidirectional"))
      (node (ref "U2") (pin "16") (pinfunction "GND_16") (pintype "bidirectional"))
      (node (ref "U2") (pin "17") (pinfunction "GND_17") (pintype "bidirectional"))
      (node (ref "U2") (pin "5") (pinfunction "~{EN}_5") (pintype "bidirectional"))
      (node (ref "U2") (pin "6") (pinfunction "GND_6") (pintype "bidirectional"))
      (node (ref "U2") (pin "PAD") (pinfunction "GND_PAD") (pintype "bidirectional"))
      (node (ref "U3") (pin "GND") (pinfunction "GND_GND") (pintype "bidirectional"))
      (node (ref "U4") (pin "10") (pinfunction "GND_10") (pintype "bidirectional"))
      (node (ref "U4") (pin "11") (pinfunction "GND_11") (pintype "bidirectional"))
      (node (ref "U4") (pin "24") (pinfunction "GND_24") (pintype "bidirectional"))
      (node (ref "U4") (pin "7") (pinfunction "GND_7") (pintype "bidirectional"))
      (node (ref "U4") (pin "9") (pinfunction "GND_9") (pintype "bidirectional"))
      (node (ref "U6") (pin "2") (pinfunction "GND_2") (pintype "power_in"))
      (node (ref "U7") (pin "3") (pinfunction "GND_3") (pintype "bidirectional"))
      (node (ref "U8") (pin "2") (pinfunction "GND_2") (pintype "bidirectional"))
      (node (ref "U8") (pin "3") (pinfunction "A0_3") (pintype "bidirectional"))
      (node (ref "U8") (pin "EP") (pinfunction "GND_EP") (pintype "bidirectional"))
      (node (ref "U9") (pin "2") (pinfunction "GND_2") (pintype "bidirectional"))
      (node (ref "X1") (pin "2") (pinfunction "GND_2") (pintype "bidirectional"))
      (node (ref "X1") (pin "4") (pinfunction "GND_4") (pintype "bidirectional"))
    )
    (net (code "12") (name "LBST") (class "Default")
      (node (ref "L5") (pin "P$1") (pinfunction "1_P$1") (pintype "bidirectional"))
      (node (ref "U10") (pin "U1") (pinfunction "P0.12_U1") (pintype "bidirectional"))
      (node (ref "U2") (pin "20") (pinfunction "LBST_20") (pintype "bidirectional"))
    )
    (net (code "13") (name "LED_BLUE") (class "Default")
      (node (ref "R3") (pin "2") (pinfunction "2_2") (pintype "passive"))
      (node (ref "U10") (pin "J1") (pinfunction "P0.04/AIN2_J1") (pintype "bidirectional"))
    )
    (net (code "14") (name "LED_GREEN") (class "Default")
      (node (ref "R2") (pin "2") (pinfunction "2_2") (pintype "passive"))
      (node (ref "U10") (pin "K2") (pinfunction "P0.05/AIN3_K2") (pintype "bidirectional"))
    )
    (net (code "15") (name "LED_RED") (class "Default")
      (node (ref "R1") (pin "2") (pinfunction "2_2") (pintype "passive"))
      (node (ref "U10") (pin "H2") (pinfunction "P0.27_H2") (pintype "bidirectional"))
    )
    (net (code "16") (name "LVLD") (class "Default")
      (node (ref "TP7") (pin "P$1") (pinfunction "TESTPOINT_P$1") (pintype "bidirectional"))
      (node (ref "U10") (pin "AD22") (pinfunction "P1.00_AD22") (pintype "bidirectional"))
      (node (ref "U6") (pin "4") (pinfunction "2Y_4") (pintype "output"))
    )
    (net (code "17") (name "MCLK") (class "Default")
      (node (ref "TP19") (pin "P$1") (pinfunction "TESTPOINT_P$1") (pintype "bidirectional"))
      (node (ref "U10") (pin "AD18") (pinfunction "P0.22_AD18") (pintype "bidirectional"))
      (node (ref "U4") (pin "15") (pinfunction "MCLK_15") (pintype "bidirectional"))
    )
    (net (code "18") (name "MISO") (class "Default")
      (node (ref "TP4") (pin "P$1") (pinfunction "TESTPOINT_P$1") (pintype "bidirectional"))
      (node (ref "U1") (pin "6") (pinfunction "SDO_6") (pintype "bidirectional"))
      (node (ref "U10") (pin "N1") (pinfunction "P0.08_N1") (pintype "bidirectional"))
    )
    (net (code "19") (name "MOSI") (class "Default")
      (node (ref "TP5") (pin "P$1") (pinfunction "TESTPOINT_P$1") (pintype "bidirectional"))
      (node (ref "U1") (pin "9") (pinfunction "SDI_9") (pintype "bidirectional"))
      (node (ref "U10") (pin "L1") (pinfunction "P0.06_L1") (pintype "bidirectional"))
    )
    (net (code "20") (name "Net-(A2-ANTENNA)") (class "Default")
      (node (ref "A2") (pin "S1") (pinfunction "ANTENNA_S1") (pintype "bidirectional"))
      (node (ref "C2") (pin "1") (pinfunction "1_1") (pintype "bidirectional"))
      (node (ref "L1") (pin "1") (pinfunction "1_1") (pintype "bidirectional"))
    )
    (net (code "21") (name "Net-(C18-Pad1)") (class "Default")
      (node (ref "C18") (pin "1") (pinfunction "1_1") (pintype "bidirectional"))
      (node (ref "U4") (pin "13") (pinfunction "DVDD_13") (pintype "bidirectional"))
      (node (ref "U4") (pin "14") (pinfunction "DVDD_14") (pintype "bidirectional"))
      (node (ref "U4") (pin "23") (pinfunction "DVDD_23") (pintype "bidirectional"))
    )
    (net (code "22") (name "Net-(D2-B)") (class "Default")
      (node (ref "D2") (pin "3") (pinfunction "B_3") (pintype "output"))
      (node (ref "R3") (pin "1") (pinfunction "1_1") (pintype "passive"))
    )
    (net (code "23") (name "Net-(D2-G)") (class "Default")
      (node (ref "D2") (pin "4") (pinfunction "G_4") (pintype "output"))
      (node (ref "R2") (pin "1") (pinfunction "1_1") (pintype "passive"))
    )
    (net (code "24") (name "Net-(D2-R)") (class "Default")
      (node (ref "D2") (pin "2") (pinfunction "R_2") (pintype "output"))
      (node (ref "R1") (pin "1") (pinfunction "1_1") (pintype "passive"))
    )
    (net (code "25") (name "Net-(L2-Pad2)") (class "Default")
      (node (ref "L2") (pin "2") (pinfunction "2_2") (pintype "bidirectional"))
      (node (ref "L4") (pin "1") (pinfunction "1_1") (pintype "bidirectional"))
    )
    (net (code "26") (name "Net-(Q1A-D)") (class "Default")
      (node (ref "Q1") (pin "6") (pinfunction "D_6") (pintype "passive"))
      (node (ref "U8") (pin "1") (pinfunction "VCC_1") (pintype "bidirectional"))
    )
    (net (code "27") (name "Net-(Q1B-D)") (class "Default")
      (node (ref "Q1") (pin "3") (pinfunction "D_3") (pintype "passive"))
      (node (ref "U3") (pin "VCC") (pinfunction "VCC_VCC") (pintype "bidirectional"))
    )
    (net (code "28") (name "Net-(Q3A-D)") (class "Default")
      (node (ref "Q3") (pin "6") (pinfunction "D_6") (pintype "passive"))
      (node (ref "U8") (pin "5") (pinfunction "SCL_5") (pintype "bidirectional"))
    )
    (net (code "29") (name "Net-(Q3B-D)") (class "Default")
      (node (ref "Q3") (pin "3") (pinfunction "D_3") (pintype "passive"))
      (node (ref "U8") (pin "6") (pinfunction "SDA_6") (pintype "bidirectional"))
    )
    (net (code "30") (name "Net-(Q4A-D)") (class "Default")
      (node (ref "C17") (pin "1") (pinfunction "1_1") (pintype "bidirectional"))
      (node (ref "C19") (pin "1") (pinfunction "1_1") (pintype "bidirectional"))
      (node (ref "Q4") (pin "6") (pinfunction "D_6") (pintype "passive"))
      (node (ref "U4") (pin "12") (pinfunction "IOVDD_12") (pintype "bidirectional"))
      (node (ref "U4") (pin "8") (pinfunction "AVDD_8") (pintype "bidirectional"))
      (node (ref "U6") (pin "5") (pinfunction "VCC_5") (pintype "power_in"))
      (node (ref "U9") (pin "1") (pinfunction "VOUT_1") (pintype "bidirectional"))
    )
    (net (code "31") (name "Net-(Q5A-D)") (class "Default")
      (node (ref "C11") (pin "1") (pinfunction "1_1") (pintype "bidirectional"))
      (node (ref "C25") (pin "1") (pinfunction "1_1") (pintype "bidirectional"))
      (node (ref "Q5") (pin "6") (pinfunction "D_6") (pintype "passive"))
      (node (ref "U2") (pin "19") (pinfunction "VSTOR_19") (pintype "bidirectional"))
      (node (ref "U2") (pin "3") (pinfunction "VOC_SAMP_3") (pintype "bidirectional"))
    )
    (net (code "32") (name "Net-(Q5A-G)") (class "Default")
      (node (ref "Q5") (pin "2") (pinfunction "G_2") (pintype "passive"))
      (node (ref "Q5") (pin "5") (pinfunction "G_5") (pintype "passive"))
      (node (ref "U2") (pin "9") (pinfunction "~{VBAT_SEC_ON}_9") (pintype "bidirectional"))
    )
    (net (code "33") (name "Net-(Q5A-S)") (class "Default")
      (node (ref "Q5") (pin "1") (pinfunction "S_1") (pintype "passive"))
      (node (ref "Q5") (pin "4") (pinfunction "S_4") (pintype "passive"))
    )
    (net (code "34") (name "Net-(Q6A-G)") (class "Default")
      (node (ref "Q6") (pin "2") (pinfunction "G_2") (pintype "passive"))
      (node (ref "Q6") (pin "5") (pinfunction "G_5") (pintype "passive"))
      (node (ref "U2") (pin "10") (pinfunction "~{VBAT_PRI_ON}_10") (pintype "bidirectional"))
    )
    (net (code "35") (name "Net-(Q6A-S)") (class "Default")
      (node (ref "Q6") (pin "1") (pinfunction "S_1") (pintype "passive"))
      (node (ref "Q6") (pin "4") (pinfunction "S_4") (pintype "passive"))
    )
    (net (code "36") (name "Net-(S1-P$2)") (class "Default")
      (node (ref "R6") (pin "1") (pinfunction "1_1") (pintype "passive"))
      (node (ref "S1") (pin "2") (pinfunction "P$2_2") (pintype "passive"))
      (node (ref "U1") (pin "3") (pinfunction "~{EXTR}_3") (pintype "bidirectional"))
    )
    (net (code "37") (name "Net-(U1-AF)") (class "Default")
      (node (ref "C7") (pin "1") (pinfunction "1_1") (pintype "bidirectional"))
      (node (ref "U1") (pin "14") (pinfunction "AF_14") (pintype "bidirectional"))
    )
    (net (code "38") (name "Net-(U1-XI)") (class "Default")
      (node (ref "C30") (pin "1") (pinfunction "1_1") (pintype "bidirectional"))
      (node (ref "U1") (pin "16") (pinfunction "XI_16") (pintype "bidirectional"))
      (node (ref "X4") (pin "1") (pinfunction "1_1") (pintype "bidirectional"))
    )
    (net (code "39") (name "Net-(U1-XO)") (class "Default")
      (node (ref "C31") (pin "1") (pinfunction "1_1") (pintype "bidirectional"))
      (node (ref "U1") (pin "15") (pinfunction "XO_15") (pintype "bidirectional"))
      (node (ref "X4") (pin "2") (pinfunction "2_2") (pintype "bidirectional"))
    )
    (net (code "40") (name "Net-(U2-OK_HYST)") (class "Default")
      (node (ref "R12") (pin "2") (pinfunction "2_2") (pintype "passive"))
      (node (ref "R4") (pin "1") (pinfunction "1_1") (pintype "passive"))
      (node (ref "U2") (pin "11") (pinfunction "OK_HYST_11") (pintype "bidirectional"))
    )
    (net (code "41") (name "Net-(U2-OK_PROG)") (class "Default")
      (node (ref "R12") (pin "1") (pinfunction "1_1") (pintype "passive"))
      (node (ref "R13") (pin "2") (pinfunction "2_2") (pintype "passive"))
      (node (ref "U2") (pin "12") (pinfunction "OK_PROG_12") (pintype "bidirectional"))
    )
    (net (code "42") (name "Net-(U2-VBAT_OV)") (class "Default")
      (node (ref "R11") (pin "1") (pinfunction "1_1") (pintype "passive"))
      (node (ref "R14") (pin "2") (pinfunction "2_2") (pintype "passive"))
      (node (ref "U2") (pin "7") (pinfunction "VBAT_OV_7") (pintype "bidirectional"))
    )
    (net (code "43") (name "Net-(U2-VRDIV)") (class "Default")
      (node (ref "R11") (pin "2") (pinfunction "2_2") (pintype "passive"))
      (node (ref "R4") (pin "2") (pinfunction "2_2") (pintype "passive"))
      (node (ref "U2") (pin "8") (pinfunction "VRDIV_8") (pintype "bidirectional"))
    )
    (net (code "44") (name "Net-(U2-VREF_SAMP)") (class "Default")
      (node (ref "C10") (pin "1") (pinfunction "1_1") (pintype "bidirectional"))
      (node (ref "U2") (pin "4") (pinfunction "VREF_SAMP_4") (pintype "bidirectional"))
    )
    (net (code "45") (name "Net-(U7-EN)") (class "Default")
      (node (ref "R15") (pin "1") (pinfunction "1_1") (pintype "passive"))
      (node (ref "U7") (pin "6") (pinfunction "EN_6") (pintype "bidirectional"))
    )
    (net (code "46") (name "Net-(U7-SEL)") (class "Default")
      (node (ref "R10") (pin "2") (pinfunction "2_2") (pintype "passive"))
      (node (ref "U7") (pin "4") (pinfunction "SEL_4") (pintype "bidirectional"))
    )
    (net (code "47") (name "Net-(U10-ANT)") (class "Default")
      (node (ref "C1") (pin "1") (pinfunction "1_1") (pintype "bidirectional"))
      (node (ref "L1") (pin "2") (pinfunction "2_2") (pintype "bidirectional"))
      (node (ref "U10") (pin "H23") (pinfunction "ANT_H23") (pintype "bidirectional"))
    )
    (net (code "48") (name "Net-(U10-DCC)") (class "Default")
      (node (ref "L4") (pin "2") (pinfunction "2_2") (pintype "bidirectional"))
      (node (ref "U10") (pin "B3") (pinfunction "DCC_B3") (pintype "bidirectional"))
    )
    (net (code "49") (name "Net-(U10-DEC1)") (class "Default")
      (node (ref "C15") (pin "1") (pinfunction "1_1") (pintype "bidirectional"))
      (node (ref "U10") (pin "C1") (pinfunction "DEC1_C1") (pintype "bidirectional"))
    )
    (net (code "50") (name "Net-(U10-DEC3)") (class "Default")
      (node (ref "C8") (pin "1") (pinfunction "1_1") (pintype "bidirectional"))
      (node (ref "U10") (pin "D23") (pinfunction "DEC3_D23") (pintype "bidirectional"))
    )
    (net (code "51") (name "Net-(U10-DEC4)") (class "Default")
      (node (ref "C12") (pin "1") (pinfunction "1_1") (pintype "bidirectional"))
      (node (ref "C21") (pin "1") (pinfunction "1_1") (pintype "bidirectional"))
      (node (ref "L2") (pin "1") (pinfunction "1_1") (pintype "bidirectional"))
      (node (ref "U10") (pin "B5") (pinfunction "DEC4_B5") (pintype "bidirectional"))
      (node (ref "U10") (pin "E24") (pinfunction "DEC6_E24") (pintype "bidirectional"))
    )
    (net (code "52") (name "Net-(U10-DEC5)") (class "Default")
      (node (ref "C9") (pin "1") (pinfunction "1_1") (pintype "bidirectional"))
      (node (ref "U10") (pin "N24") (pinfunction "DEC5_N24") (pintype "bidirectional"))
    )
    (net (code "53") (name "Net-(U10-P0.00{slash}XL1)") (class "Default")
      (node (ref "C6") (pin "2") (pinfunction "2_2") (pintype "bidirectional"))
      (node (ref "U10") (pin "D2") (pinfunction "P0.00/XL1_D2") (pintype "bidirectional"))
      (node (ref "X3") (pin "A") (pinfunction "1_A") (pintype "bidirectional"))
    )
    (net (code "54") (name "Net-(U10-P0.01{slash}XL2)") (class "Default")
      (node (ref "C5") (pin "2") (pinfunction "2_2") (pintype "bidirectional"))
      (node (ref "U10") (pin "F2") (pinfunction "P0.01/XL2_F2") (pintype "bidirectional"))
      (node (ref "X3") (pin "B") (pinfunction "2_B") (pintype "bidirectional"))
    )
    (net (code "55") (name "Net-(U10-XC1)") (class "Default")
      (node (ref "C3") (pin "2") (pinfunction "2_2") (pintype "bidirectional"))
      (node (ref "U10") (pin "B24") (pinfunction "XC1_B24") (pintype "bidirectional"))
      (node (ref "X1") (pin "3") (pinfunction "2_3") (pintype "bidirectional"))
    )
    (net (code "56") (name "Net-(U10-XC2)") (class "Default")
      (node (ref "C4") (pin "2") (pinfunction "2_2") (pintype "bidirectional"))
      (node (ref "U10") (pin "A23") (pinfunction "XC2_A23") (pintype "bidirectional"))
      (node (ref "X1") (pin "1") (pinfunction "1_1") (pintype "bidirectional"))
    )
    (net (code "57") (name "PCLKO") (class "Default")
      (node (ref "TP18") (pin "P$1") (pinfunction "TESTPOINT_P$1") (pintype "bidirectional"))
      (node (ref "U10") (pin "AD16") (pinfunction "P0.20_AD16") (pintype "bidirectional"))
      (node (ref "U4") (pin "16") (pinfunction "PCLKO_16") (pintype "bidirectional"))
    )
    (net (code "58") (name "PIR_OUT") (class "Default")
      (node (ref "TP22") (pin "P$1") (pinfunction "TESTPOINT_P$1") (pintype "bidirectional"))
      (node (ref "U10") (pin "A20") (pinfunction "P1.10_A20") (pintype "bidirectional"))
      (node (ref "U3") (pin "OUT") (pinfunction "OUT_OUT") (pintype "bidirectional"))
    )
    (net (code "59") (name "RTC_CS") (class "Default")
      (node (ref "TP6") (pin "P$1") (pinfunction "TESTPOINT_P$1") (pintype "bidirectional"))
      (node (ref "U1") (pin "12") (pinfunction "~{CS}_12") (pintype "bidirectional"))
      (node (ref "U10") (pin "B17") (pinfunction "P1.12_B17") (pintype "bidirectional"))
    )
    (net (code "60") (name "SCK") (class "Default")
      (node (ref "TP3") (pin "P$1") (pinfunction "TESTPOINT_P$1") (pintype "bidirectional"))
      (node (ref "U1") (pin "7") (pinfunction "SCL_7") (pintype "bidirectional"))
      (node (ref "U10") (pin "M2") (pinfunction "P0.07_M2") (pintype "bidirectional"))
    )
    (net (code "61") (name "SCL") (class "Default")
      (node (ref "Q2") (pin "4") (pinfunction "S_4") (pintype "passive"))
      (node (ref "Q3") (pin "1") (pinfunction "S_1") (pintype "passive"))
      (node (ref "R20") (pin "1") (pinfunction "1_1") (pintype "passive"))
      (node (ref "TP2") (pin "P$1") (pinfunction "TESTPOINT_P$1") (pintype "bidirectional"))
      (node (ref "U10") (pin "AC9") (pinfunction "P0.14_AC9") (pintype "bidirectional"))
    )
    (net (code "62") (name "SDA") (class "Default")
      (node (ref "Q2") (pin "1") (pinfunction "S_1") (pintype "passive"))
      (node (ref "Q3") (pin "4") (pinfunction "S_4") (pintype "passive"))
      (node (ref "R19") (pin "1") (pinfunction "1_1") (pintype "passive"))
      (node (ref "TP1") (pin "P$1") (pinfunction "TESTPOINT_P$1") (pintype "bidirectional"))
      (node (ref "U10") (pin "AD8") (pinfunction "P0.13_AD8") (pintype "bidirectional"))
    )
    (net (code "63") (name "SW") (class "Default")
      (node (ref "L3") (pin "P$2") (pinfunction "2_P$2") (pintype "bidirectional"))
      (node (ref "TP25") (pin "P$1") (pinfunction "TESTPOINT_P$1") (pintype "bidirectional"))
      (node (ref "U10") (pin "R1") (pinfunction "P1.09_R1") (pintype "bidirectional"))
      (node (ref "U7") (pin "2") (pinfunction "LX_2") (pintype "bidirectional"))
    )
    (net (code "64") (name "SWDCLK") (class "Default")
      (node (ref "J1") (pin "4") (pinfunction "SWDCLK_4") (pintype "bidirectional"))
      (node (ref "U10") (pin "AA24") (pinfunction "SWDCLK_AA24") (pintype "bidirectional"))
    )
    (net (code "65") (name "SWDIO") (class "Default")
      (node (ref "J1") (pin "2") (pinfunction "SWDIO_2") (pintype "bidirectional"))
      (node (ref "U10") (pin "AC24") (pinfunction "SWDIO_AC24") (pintype "bidirectional"))
    )
    (net (code "66") (name "VBAT") (class "Default")
      (node (ref "BT2") (pin "1") (pinfunction "+_1") (pintype "bidirectional"))
      (node (ref "BT2") (pin "2") (pinfunction "+_2") (pintype "bidirectional"))
      (node (ref "Q6") (pin "6") (pinfunction "D_6") (pintype "passive"))
      (node (ref "U1") (pin "5") (pinfunction "VBAT_5") (pintype "bidirectional"))
      (node (ref "U10") (pin "A10") (pinfunction "P0.29/AIN5_A10") (pintype "bidirectional"))
      (node (ref "U2") (pin "14") (pinfunction "VBAT_PRI_14") (pintype "bidirectional"))
    )
    (net (code "67") (name "VBAT_OK") (class "Default")
      (node (ref "U10") (pin "T2") (pinfunction "P0.11_T2") (pintype "bidirectional"))
      (node (ref "U2") (pin "13") (pinfunction "VBAT_OK_13") (pintype "bidirectional"))
    )
    (net (code "68") (name "VCC") (class "Default")
      (node (ref "C13") (pin "1") (pinfunction "1_1") (pintype "bidirectional"))
      (node (ref "C14") (pin "1") (pinfunction "1_1") (pintype "bidirectional"))
      (node (ref "C16") (pin "1") (pinfunction "1_1") (pintype "bidirectional"))
      (node (ref "C20") (pin "1") (pinfunction "1_1") (pintype "bidirectional"))
      (node (ref "C22") (pin "1") (pinfunction "1_1") (pintype "bidirectional"))
      (node (ref "C23") (pin "1") (pinfunction "1_1") (pintype "bidirectional"))
      (node (ref "C24") (pin "1") (pinfunction "1_1") (pintype "bidirectional"))
      (node (ref "C28") (pin "1") (pinfunction "1_1") (pintype "bidirectional"))
      (node (ref "C29") (pin "1") (pinfunction "1_1") (pintype "bidirectional"))
      (node (ref "D2") (pin "1") (pinfunction "VDD_1") (pintype "bidirectional"))
      (node (ref "J1") (pin "1") (pinfunction "VCC_1") (pintype "bidirectional"))
      (node (ref "Q1") (pin "1") (pinfunction "S_1") (pintype "passive"))
      (node (ref "Q1") (pin "4") (pinfunction "S_4") (pintype "passive"))
      (node (ref "Q4") (pin "1") (pinfunction "S_1") (pintype "passive"))
      (node (ref "R16") (pin "2") (pinfunction "2_2") (pintype "passive"))
      (node (ref "R17") (pin "2") (pinfunction "2_2") (pintype "passive"))
      (node (ref "R18") (pin "2") (pinfunction "2_2") (pintype "passive"))
      (node (ref "R19") (pin "2") (pinfunction "2_2") (pintype "passive"))
      (node (ref "R20") (pin "2") (pinfunction "2_2") (pintype "passive"))
      (node (ref "R5") (pin "2") (pinfunction "2_2") (pintype "passive"))
      (node (ref "R6") (pin "2") (pinfunction "2_2") (pintype "passive"))
      (node (ref "R7") (pin "2") (pinfunction "2_2") (pintype "passive"))
      (node (ref "R8") (pin "2") (pinfunction "2_2") (pintype "passive"))
      (node (ref "TP26") (pin "P$1") (pinfunction "TESTPOINT_P$1") (pintype "bidirectional"))
      (node (ref "U1") (pin "13") (pinfunction "VCC_13") (pintype "bidirectional"))
      (node (ref "U10") (pin "A22") (pinfunction "VDD_A22") (pintype "bidirectional"))
      (node (ref "U10") (pin "AD14") (pinfunction "VDD_AD14") (pintype "bidirectional"))
      (node (ref "U10") (pin "AD23") (pinfunction "VDD_AD23") (pintype "bidirectional"))
      (node (ref "U10") (pin "B1") (pinfunction "VDD_B1") (pintype "bidirectional"))
      (node (ref "U10") (pin "W1") (pinfunction "VDD_W1") (pintype "bidirectional"))
      (node (ref "U10") (pin "Y2") (pinfunction "VDDH_Y2") (pintype "bidirectional"))
      (node (ref "U7") (pin "1") (pinfunction "OUT_1") (pintype "bidirectional"))
      (node (ref "U9") (pin "4") (pinfunction "VIN_4") (pintype "bidirectional"))
      (node (ref "U9") (pin "5") (pinfunction "VBIAS_5") (pintype "bidirectional"))
    )
    (net (code "69") (name "VSEC") (class "Default")
      (node (ref "BT1") (pin "+") (pinfunction "+_+") (pintype "bidirectional"))
      (node (ref "U10") (pin "A8") (pinfunction "P0.31/AIN7_A8") (pintype "bidirectional"))
      (node (ref "U2") (pin "18") (pinfunction "VBAT_SEC_18") (pintype "bidirectional"))
    )
    (net (code "70") (name "VSOL") (class "Default")
      (node (ref "C26") (pin "1") (pinfunction "1_1") (pintype "bidirectional"))
      (node (ref "D1") (pin "+") (pinfunction "V+_+") (pintype "bidirectional"))
      (node (ref "L5") (pin "P$2") (pinfunction "2_P$2") (pintype "bidirectional"))
      (node (ref "TP23") (pin "P$1") (pinfunction "TESTPOINT_P$1") (pintype "bidirectional"))
      (node (ref "U10") (pin "B9") (pinfunction "P0.30/AIN6_B9") (pintype "bidirectional"))
      (node (ref "U2") (pin "2") (pinfunction "VIN_DC_2") (pintype "bidirectional"))
    )
    (net (code "71") (name "VSW") (class "Default")
      (node (ref "C27") (pin "1") (pinfunction "1_1") (pintype "bidirectional"))
      (node (ref "L3") (pin "P$1") (pinfunction "1_P$1") (pintype "bidirectional"))
      (node (ref "Q5") (pin "3") (pinfunction "D_3") (pintype "passive"))
      (node (ref "Q6") (pin "3") (pinfunction "D_3") (pintype "passive"))
      (node (ref "R15") (pin "2") (pinfunction "2_2") (pintype "passive"))
      (node (ref "U7") (pin "5") (pinfunction "IN_5") (pintype "bidirectional"))
    )
    (net (code "72") (name "WDI") (class "Default")
      (node (ref "R8") (pin "1") (pinfunction "1_1") (pintype "passive"))
      (node (ref "TP16") (pin "P$1") (pinfunction "TESTPOINT_P$1") (pintype "bidirectional"))
      (node (ref "U1") (pin "2") (pinfunction "WDI_2") (pintype "bidirectional"))
      (node (ref "U10") (pin "A12") (pinfunction "P0.02/AIN0_A12") (pintype "bidirectional"))
    )
    (net (code "73") (name "unconnected-(J1-SWO-Pad6)") (class "Default")
      (node (ref "J1") (pin "6") (pinfunction "SWO_6") (pintype "bidirectional"))
    )
    (net (code "74") (name "unconnected-(U4-D4-Pad21)") (class "Default")
      (node (ref "U4") (pin "21") (pinfunction "D4_21") (pintype "bidirectional"))
    )
    (net (code "75") (name "unconnected-(U4-D5-Pad22)") (class "Default")
      (node (ref "U4") (pin "22") (pinfunction "D5_22") (pintype "bidirectional"))
    )
    (net (code "76") (name "unconnected-(U4-D6-Pad25)") (class "Default")
      (node (ref "U4") (pin "25") (pinfunction "D6_25") (pintype "bidirectional"))
    )
    (net (code "77") (name "unconnected-(U4-D7-Pad26)") (class "Default")
      (node (ref "U4") (pin "26") (pinfunction "D7_26") (pintype "bidirectional"))
    )
    (net (code "78") (name "unconnected-(U10-D+-PadAD6)") (class "Default")
      (node (ref "U10") (pin "AD6") (pinfunction "D+_AD6") (pintype "bidirectional"))
    )
    (net (code "79") (name "unconnected-(U10-D--PadAD4)") (class "Default")
      (node (ref "U10") (pin "AD4") (pinfunction "D-_AD4") (pintype "bidirectional"))
    )
    (net (code "80") (name "unconnected-(U10-DCCH-PadAB2)") (class "Default")
      (node (ref "U10") (pin "AB2") (pinfunction "DCCH_AB2") (pintype "bidirectional"))
    )
    (net (code "81") (name "unconnected-(U10-DEC2-PadA18)") (class "Default")
      (node (ref "U10") (pin "A18") (pinfunction "DEC2_A18") (pintype "bidirectional"))
    )
    (net (code "82") (name "unconnected-(U10-DECUSB-PadAC5)") (class "Default")
      (node (ref "U10") (pin "AC5") (pinfunction "DECUSB_AC5") (pintype "bidirectional"))
    )
    (net (code "83") (name "unconnected-(U10-P0.09{slash}NFC1-PadL24)") (class "Default")
      (node (ref "U10") (pin "L24") (pinfunction "P0.09/NFC1_L24") (pintype "bidirectional"))
    )
    (net (code "84") (name "unconnected-(U10-P0.10{slash}NFC2-PadJ24)") (class "Default")
      (node (ref "U10") (pin "J24") (pinfunction "P0.10/NFC2_J24") (pintype "bidirectional"))
    )
    (net (code "85") (name "unconnected-(U10-P0.19-PadAC15)") (class "Default")
      (node (ref "U10") (pin "AC15") (pinfunction "P0.19_AC15") (pintype "bidirectional"))
    )
    (net (code "86") (name "unconnected-(U10-P0.21-PadAC17)") (class "Default")
      (node (ref "U10") (pin "AC17") (pinfunction "P0.21_AC17") (pintype "bidirectional"))
    )
    (net (code "87") (name "unconnected-(U10-P0.26-PadG1)") (class "Default")
      (node (ref "U10") (pin "G1") (pinfunction "P0.26_G1") (pintype "bidirectional"))
    )
    (net (code "88") (name "unconnected-(U10-P1.01-PadY23)") (class "Default")
      (node (ref "U10") (pin "Y23") (pinfunction "P1.01_Y23") (pintype "bidirectional"))
    )
    (net (code "89") (name "unconnected-(U10-P1.02-PadW24)") (class "Default")
      (node (ref "U10") (pin "W24") (pinfunction "P1.02_W24") (pintype "bidirectional"))
    )
    (net (code "90") (name "unconnected-(U10-P1.03-PadV23)") (class "Default")
      (node (ref "U10") (pin "V23") (pinfunction "P1.03_V23") (pintype "bidirectional"))
    )
    (net (code "91") (name "unconnected-(U10-P1.04-PadU24)") (class "Default")
      (node (ref "U10") (pin "U24") (pinfunction "P1.04_U24") (pintype "bidirectional"))
    )
    (net (code "92") (name "unconnected-(U10-P1.05-PadT23)") (class "Default")
      (node (ref "U10") (pin "T23") (pinfunction "P1.05_T23") (pintype "bidirectional"))
    )
    (net (code "93") (name "unconnected-(U10-P1.06-PadR24)") (class "Default")
      (node (ref "U10") (pin "R24") (pinfunction "P1.06_R24") (pintype "bidirectional"))
    )
    (net (code "94") (name "unconnected-(U10-P1.07-PadP23)") (class "Default")
      (node (ref "U10") (pin "P23") (pinfunction "P1.07_P23") (pintype "bidirectional"))
    )
    (net (code "95") (name "unconnected-(U10-P1.08-PadP2)") (class "Default")
      (node (ref "U10") (pin "P2") (pinfunction "P1.08_P2") (pintype "bidirectional"))
    )
    (net (code "96") (name "~{CAM_EN}") (class "Default")
      (node (ref "Q2") (pin "2") (pinfunction "G_2") (pintype "passive"))
      (node (ref "Q2") (pin "5") (pinfunction "G_5") (pintype "passive"))
      (node (ref "Q4") (pin "2") (pinfunction "G_2") (pintype "passive"))
      (node (ref "R18") (pin "1") (pinfunction "1_1") (pintype "passive"))
      (node (ref "U10") (pin "AD10") (pinfunction "P0.15_AD10") (pintype "bidirectional"))
    )
    (net (code "97") (name "~{FVLD}") (class "Default")
      (node (ref "TP12") (pin "P$1") (pinfunction "TESTPOINT_P$1") (pintype "bidirectional"))
      (node (ref "U4") (pin "5") (pinfunction "FVLD_5") (pintype "bidirectional"))
      (node (ref "U6") (pin "1") (pinfunction "1A_1") (pintype "input"))
    )
    (net (code "98") (name "~{LT_EN}") (class "Default")
      (node (ref "Q1") (pin "2") (pinfunction "G_2") (pintype "passive"))
      (node (ref "Q3") (pin "2") (pinfunction "G_2") (pintype "passive"))
      (node (ref "Q3") (pin "5") (pinfunction "G_5") (pintype "passive"))
      (node (ref "R16") (pin "1") (pinfunction "1_1") (pintype "passive"))
      (node (ref "TP10") (pin "P$1") (pinfunction "TESTPOINT_P$1") (pintype "bidirectional"))
      (node (ref "U10") (pin "B11") (pinfunction "P0.28/AIN4_B11") (pintype "bidirectional"))
    )
    (net (code "99") (name "~{LT_INT}") (class "Default")
      (node (ref "R5") (pin "1") (pinfunction "1_1") (pintype "passive"))
      (node (ref "TP21") (pin "P$1") (pinfunction "TESTPOINT_P$1") (pintype "bidirectional"))
      (node (ref "U10") (pin "B13") (pinfunction "P0.03/AIN1_B13") (pintype "bidirectional"))
      (node (ref "U8") (pin "4") (pinfunction "~{INT}_4") (pintype "bidirectional"))
    )
    (net (code "100") (name "~{LVLD}") (class "Default")
      (node (ref "TP9") (pin "P$1") (pinfunction "TESTPOINT_P$1") (pintype "bidirectional"))
      (node (ref "U4") (pin "4") (pinfunction "LVLD_4") (pintype "bidirectional"))
      (node (ref "U6") (pin "3") (pinfunction "2A_3") (pintype "input"))
    )
    (net (code "101") (name "~{PIR_EN}") (class "Default")
      (node (ref "Q1") (pin "5") (pinfunction "G_5") (pintype "passive"))
      (node (ref "R17") (pin "1") (pinfunction "1_1") (pintype "passive"))
      (node (ref "TP11") (pin "P$1") (pinfunction "TESTPOINT_P$1") (pintype "bidirectional"))
      (node (ref "U10") (pin "B19") (pinfunction "P1.11_B19") (pintype "bidirectional"))
    )
    (net (code "102") (name "~{RST}") (class "Default")
      (node (ref "J1") (pin "3") (pinfunction "~{RESET}_3") (pintype "bidirectional"))
      (node (ref "R7") (pin "1") (pinfunction "1_1") (pintype "passive"))
      (node (ref "TP17") (pin "P$1") (pinfunction "TESTPOINT_P$1") (pintype "bidirectional"))
      (node (ref "U1") (pin "1") (pinfunction "~{RST}_1") (pintype "bidirectional"))
      (node (ref "U10") (pin "AC13") (pinfunction "P0.18_AC13") (pintype "bidirectional"))
    )
    (net (code "103") (name "~{RTC_IRQ1}") (class "Default")
      (node (ref "TP13") (pin "P$1") (pinfunction "TESTPOINT_P$1") (pintype "bidirectional"))
      (node (ref "U1") (pin "11") (pinfunction "FOUT/~{IRQ1}_11") (pintype "bidirectional"))
      (node (ref "U10") (pin "A16") (pinfunction "P1.13_A16") (pintype "bidirectional"))
    )
    (net (code "104") (name "~{RTC_IRQ2}") (class "Default")
      (node (ref "TP14") (pin "P$1") (pinfunction "TESTPOINT_P$1") (pintype "bidirectional"))
      (node (ref "U1") (pin "4") (pinfunction "~{IRQ2}_4") (pintype "bidirectional"))
      (node (ref "U10") (pin "A14") (pinfunction "P1.15_A14") (pintype "bidirectional"))
    )
    (net (code "105") (name "~{RTC_IRQ3}") (class "Default")
      (node (ref "TP15") (pin "P$1") (pinfunction "TESTPOINT_P$1") (pintype "bidirectional"))
      (node (ref "U1") (pin "8") (pinfunction "CLKOUT/~{IRQ3}_8") (pintype "bidirectional"))
      (node (ref "U10") (pin "B15") (pinfunction "P1.14_B15") (pintype "bidirectional"))
    )
  )
)
